# binary_clock.net
KiCad netlist of a schematic drawn in EAGLE
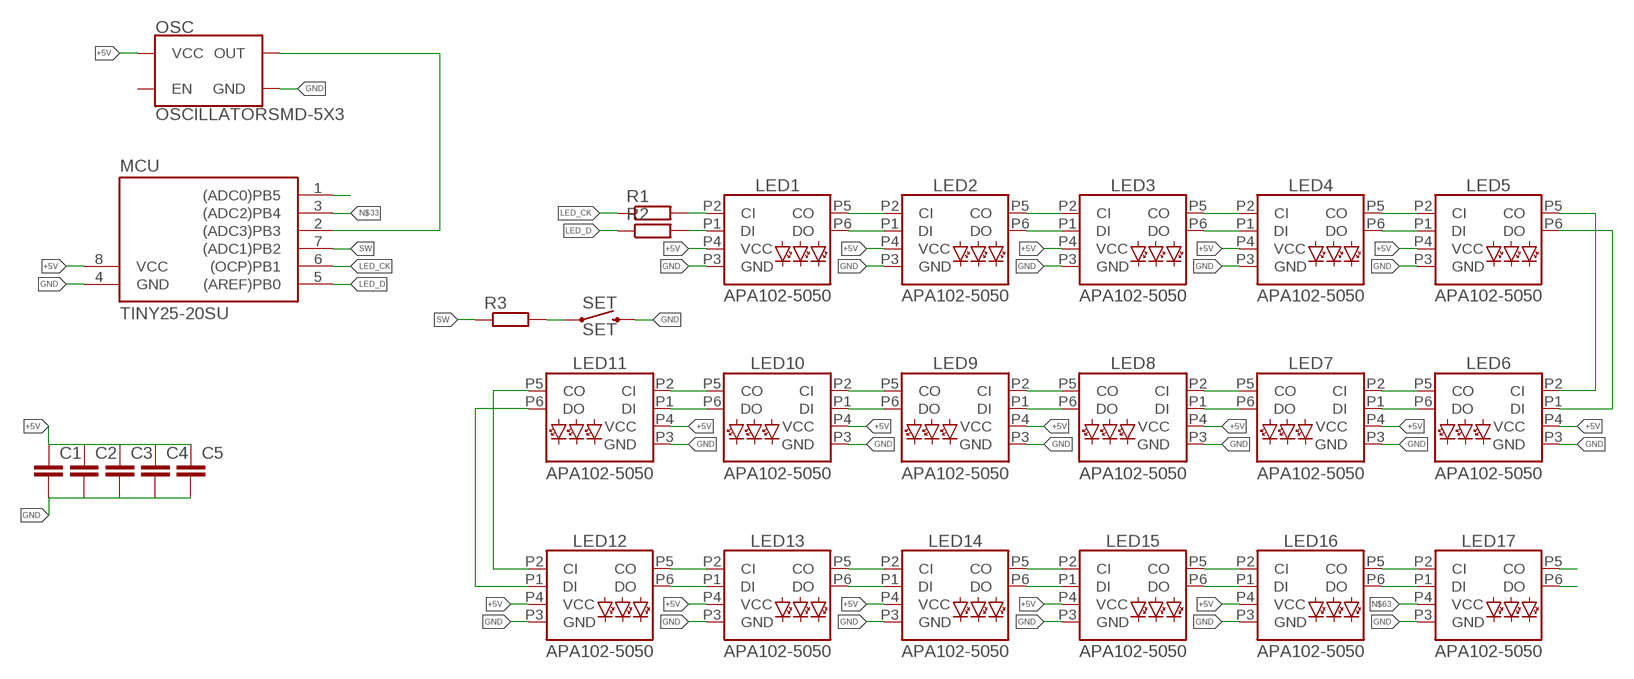
[diagram p0: schematic, sheet 1]

(export (version "E")
  (design (tool "Eeschema 10.0.6"))
  (components
    (comp (ref "C1")
      (value "C-EUC0603K")
      (footprint "eagle-import:C0603K")
      (libsource (lib "eagle-import") (part "C-EUC0603K"))
    )
    (comp (ref "C2")
      (value "C-EUC0603K")
      (footprint "eagle-import:C0603K")
      (libsource (lib "eagle-import") (part "C-EUC0603K"))
    )
    (comp (ref "C3")
      (value "C-EUC0603K")
      (footprint "eagle-import:C0603K")
      (libsource (lib "eagle-import") (part "C-EUC0603K"))
    )
    (comp (ref "C4")
      (value "C-EUC0603K")
      (footprint "eagle-import:C0603K")
      (libsource (lib "eagle-import") (part "C-EUC0603K"))
    )
    (comp (ref "C5")
      (value "C-EUC0603K")
      (footprint "eagle-import:C0603K")
      (libsource (lib "eagle-import") (part "C-EUC0603K"))
    )
    (comp (ref "LED1")
      (value "APA102-5050")
      (footprint "eagle-import:APA102-5050")
      (libsource (lib "eagle-import") (part "APA102-5050"))
    )
    (comp (ref "LED2")
      (value "APA102-5050")
      (footprint "eagle-import:APA102-5050")
      (libsource (lib "eagle-import") (part "APA102-5050"))
    )
    (comp (ref "LED3")
      (value "APA102-5050")
      (footprint "eagle-import:APA102-5050")
      (libsource (lib "eagle-import") (part "APA102-5050"))
    )
    (comp (ref "LED4")
      (value "APA102-5050")
      (footprint "eagle-import:APA102-5050")
      (libsource (lib "eagle-import") (part "APA102-5050"))
    )
    (comp (ref "LED5")
      (value "APA102-5050")
      (footprint "eagle-import:APA102-5050")
      (libsource (lib "eagle-import") (part "APA102-5050"))
    )
    (comp (ref "LED6")
      (value "APA102-5050")
      (footprint "eagle-import:APA102-5050")
      (libsource (lib "eagle-import") (part "APA102-5050"))
    )
    (comp (ref "LED7")
      (value "APA102-5050")
      (footprint "eagle-import:APA102-5050")
      (libsource (lib "eagle-import") (part "APA102-5050"))
    )
    (comp (ref "LED8")
      (value "APA102-5050")
      (footprint "eagle-import:APA102-5050")
      (libsource (lib "eagle-import") (part "APA102-5050"))
    )
    (comp (ref "LED9")
      (value "APA102-5050")
      (footprint "eagle-import:APA102-5050")
      (libsource (lib "eagle-import") (part "APA102-5050"))
    )
    (comp (ref "LED10")
      (value "APA102-5050")
      (footprint "eagle-import:APA102-5050")
      (libsource (lib "eagle-import") (part "APA102-5050"))
    )
    (comp (ref "LED11")
      (value "APA102-5050")
      (footprint "eagle-import:APA102-5050")
      (libsource (lib "eagle-import") (part "APA102-5050"))
    )
    (comp (ref "LED12")
      (value "APA102-5050")
      (footprint "eagle-import:APA102-5050")
      (libsource (lib "eagle-import") (part "APA102-5050"))
    )
    (comp (ref "LED13")
      (value "APA102-5050")
      (footprint "eagle-import:APA102-5050")
      (libsource (lib "eagle-import") (part "APA102-5050"))
    )
    (comp (ref "LED14")
      (value "APA102-5050")
      (footprint "eagle-import:APA102-5050")
      (libsource (lib "eagle-import") (part "APA102-5050"))
    )
    (comp (ref "LED15")
      (value "APA102-5050")
      (footprint "eagle-import:APA102-5050")
      (libsource (lib "eagle-import") (part "APA102-5050"))
    )
    (comp (ref "LED16")
      (value "APA102-5050")
      (footprint "eagle-import:APA102-5050")
      (libsource (lib "eagle-import") (part "APA102-5050"))
    )
    (comp (ref "LED17")
      (value "APA102-5050")
      (footprint "eagle-import:APA102-5050")
      (libsource (lib "eagle-import") (part "APA102-5050"))
    )
    (comp (ref "MCU")
      (value "TINY25-20SU")
      (footprint "eagle-import:SOIC8")
      (libsource (lib "eagle-import") (part "TINY25-20SU"))
    )
    (comp (ref "OSC")
      (value "OSCILLATORSMD-5X3")
      (footprint "eagle-import:OSCILLATOR-SMD-5X3.2")
      (libsource (lib "eagle-import") (part "OSCILLATORSMD-5X3"))
    )
    (comp (ref "R1")
      (value "R-EU_R1206")
      (footprint "eagle-import:R1206")
      (libsource (lib "eagle-import") (part "R-EU_R1206"))
    )
    (comp (ref "R2")
      (value "R-EU_R1206")
      (footprint "eagle-import:R1206")
      (libsource (lib "eagle-import") (part "R-EU_R1206"))
    )
    (comp (ref "R3")
      (value "R-EU_R1206")
      (footprint "eagle-import:R1206")
      (libsource (lib "eagle-import") (part "R-EU_R1206"))
    )
    (comp (ref "SET")
      (value "SET")
      (footprint "eagle-import:TACTILE_SWITCH_SMD_5.2MM")
      (libsource (lib "eagle-import") (part "MOMENTARY-SWITCH-SPST-SMD-5.2-REDUNDANT"))
    )
  )
  (nets
    (net (code "1") (name "+5V") (class "Default")
      (node (ref "C1") (pin "1") (pinfunction "1_1") (pintype "passive"))
      (node (ref "C2") (pin "1") (pinfunction "1_1") (pintype "passive"))
      (node (ref "C3") (pin "1") (pinfunction "1_1") (pintype "passive"))
      (node (ref "C4") (pin "1") (pinfunction "1_1") (pintype "passive"))
      (node (ref "C5") (pin "1") (pinfunction "1_1") (pintype "passive"))
      (node (ref "LED1") (pin "P4") (pinfunction "VCC_P4") (pintype "bidirectional"))
      (node (ref "LED10") (pin "P4") (pinfunction "VCC_P4") (pintype "bidirectional"))
      (node (ref "LED11") (pin "P4") (pinfunction "VCC_P4") (pintype "bidirectional"))
      (node (ref "LED12") (pin "P4") (pinfunction "VCC_P4") (pintype "bidirectional"))
      (node (ref "LED13") (pin "P4") (pinfunction "VCC_P4") (pintype "bidirectional"))
      (node (ref "LED14") (pin "P4") (pinfunction "VCC_P4") (pintype "bidirectional"))
      (node (ref "LED15") (pin "P4") (pinfunction "VCC_P4") (pintype "bidirectional"))
      (node (ref "LED16") (pin "P4") (pinfunction "VCC_P4") (pintype "bidirectional"))
      (node (ref "LED2") (pin "P4") (pinfunction "VCC_P4") (pintype "bidirectional"))
      (node (ref "LED3") (pin "P4") (pinfunction "VCC_P4") (pintype "bidirectional"))
      (node (ref "LED4") (pin "P4") (pinfunction "VCC_P4") (pintype "bidirectional"))
      (node (ref "LED5") (pin "P4") (pinfunction "VCC_P4") (pintype "bidirectional"))
      (node (ref "LED6") (pin "P4") (pinfunction "VCC_P4") (pintype "bidirectional"))
      (node (ref "LED7") (pin "P4") (pinfunction "VCC_P4") (pintype "bidirectional"))
      (node (ref "LED8") (pin "P4") (pinfunction "VCC_P4") (pintype "bidirectional"))
      (node (ref "LED9") (pin "P4") (pinfunction "VCC_P4") (pintype "bidirectional"))
      (node (ref "MCU") (pin "8") (pinfunction "VCC_8") (pintype "power_in"))
      (node (ref "OSC") (pin "4") (pinfunction "VCC_4") (pintype "bidirectional"))
    )
    (net (code "2") (name "GND") (class "Default")
      (node (ref "C1") (pin "2") (pinfunction "2_2") (pintype "passive"))
      (node (ref "C2") (pin "2") (pinfunction "2_2") (pintype "passive"))
      (node (ref "C3") (pin "2") (pinfunction "2_2") (pintype "passive"))
      (node (ref "C4") (pin "2") (pinfunction "2_2") (pintype "passive"))
      (node (ref "C5") (pin "2") (pinfunction "2_2") (pintype "passive"))
      (node (ref "LED1") (pin "P3") (pinfunction "GND_P3") (pintype "bidirectional"))
      (node (ref "LED10") (pin "P3") (pinfunction "GND_P3") (pintype "bidirectional"))
      (node (ref "LED11") (pin "P3") (pinfunction "GND_P3") (pintype "bidirectional"))
      (node (ref "LED12") (pin "P3") (pinfunction "GND_P3") (pintype "bidirectional"))
      (node (ref "LED13") (pin "P3") (pinfunction "GND_P3") (pintype "bidirectional"))
      (node (ref "LED14") (pin "P3") (pinfunction "GND_P3") (pintype "bidirectional"))
      (node (ref "LED15") (pin "P3") (pinfunction "GND_P3") (pintype "bidirectional"))
      (node (ref "LED16") (pin "P3") (pinfunction "GND_P3") (pintype "bidirectional"))
      (node (ref "LED17") (pin "P3") (pinfunction "GND_P3") (pintype "bidirectional"))
      (node (ref "LED2") (pin "P3") (pinfunction "GND_P3") (pintype "bidirectional"))
      (node (ref "LED3") (pin "P3") (pinfunction "GND_P3") (pintype "bidirectional"))
      (node (ref "LED4") (pin "P3") (pinfunction "GND_P3") (pintype "bidirectional"))
      (node (ref "LED5") (pin "P3") (pinfunction "GND_P3") (pintype "bidirectional"))
      (node (ref "LED6") (pin "P3") (pinfunction "GND_P3") (pintype "bidirectional"))
      (node (ref "LED7") (pin "P3") (pinfunction "GND_P3") (pintype "bidirectional"))
      (node (ref "LED8") (pin "P3") (pinfunction "GND_P3") (pintype "bidirectional"))
      (node (ref "LED9") (pin "P3") (pinfunction "GND_P3") (pintype "bidirectional"))
      (node (ref "MCU") (pin "4") (pinfunction "GND_4") (pintype "power_in"))
      (node (ref "OSC") (pin "2") (pinfunction "GND_2") (pintype "bidirectional"))
      (node (ref "SET") (pin "3") (pinfunction "2_3") (pintype "passive"))
      (node (ref "SET") (pin "4") (pinfunction "2_4") (pintype "passive"))
    )
    (net (code "3") (name "LED_CK") (class "Default")
      (node (ref "MCU") (pin "6") (pinfunction "(OCP)PB1_6") (pintype "bidirectional"))
      (node (ref "R1") (pin "1") (pinfunction "1_1") (pintype "passive"))
    )
    (net (code "4") (name "LED_D") (class "Default")
      (node (ref "MCU") (pin "5") (pinfunction "(AREF)PB0_5") (pintype "bidirectional"))
      (node (ref "R2") (pin "1") (pinfunction "1_1") (pintype "passive"))
    )
    (net (code "5") (name "N$33") (class "Default")
      (node (ref "MCU") (pin "3") (pinfunction "(ADC2)PB4_3") (pintype "bidirectional"))
    )
    (net (code "6") (name "N$63") (class "Default")
      (node (ref "LED17") (pin "P4") (pinfunction "VCC_P4") (pintype "bidirectional"))
    )
    (net (code "7") (name "Net-(LED1-CI)") (class "Default")
      (node (ref "LED1") (pin "P2") (pinfunction "CI_P2") (pintype "bidirectional"))
      (node (ref "R1") (pin "2") (pinfunction "2_2") (pintype "passive"))
    )
    (net (code "8") (name "Net-(LED1-CO)") (class "Default")
      (node (ref "LED1") (pin "P5") (pinfunction "CO_P5") (pintype "bidirectional"))
      (node (ref "LED2") (pin "P2") (pinfunction "CI_P2") (pintype "bidirectional"))
    )
    (net (code "9") (name "Net-(LED1-DI)") (class "Default")
      (node (ref "LED1") (pin "P1") (pinfunction "DI_P1") (pintype "bidirectional"))
      (node (ref "R2") (pin "2") (pinfunction "2_2") (pintype "passive"))
    )
    (net (code "10") (name "Net-(LED1-DO)") (class "Default")
      (node (ref "LED1") (pin "P6") (pinfunction "DO_P6") (pintype "bidirectional"))
      (node (ref "LED2") (pin "P1") (pinfunction "DI_P1") (pintype "bidirectional"))
    )
    (net (code "11") (name "Net-(LED2-CO)") (class "Default")
      (node (ref "LED2") (pin "P5") (pinfunction "CO_P5") (pintype "bidirectional"))
      (node (ref "LED3") (pin "P2") (pinfunction "CI_P2") (pintype "bidirectional"))
    )
    (net (code "12") (name "Net-(LED2-DO)") (class "Default")
      (node (ref "LED2") (pin "P6") (pinfunction "DO_P6") (pintype "bidirectional"))
      (node (ref "LED3") (pin "P1") (pinfunction "DI_P1") (pintype "bidirectional"))
    )
    (net (code "13") (name "Net-(LED3-CO)") (class "Default")
      (node (ref "LED3") (pin "P5") (pinfunction "CO_P5") (pintype "bidirectional"))
      (node (ref "LED4") (pin "P2") (pinfunction "CI_P2") (pintype "bidirectional"))
    )
    (net (code "14") (name "Net-(LED3-DO)") (class "Default")
      (node (ref "LED3") (pin "P6") (pinfunction "DO_P6") (pintype "bidirectional"))
      (node (ref "LED4") (pin "P1") (pinfunction "DI_P1") (pintype "bidirectional"))
    )
    (net (code "15") (name "Net-(LED4-CO)") (class "Default")
      (node (ref "LED4") (pin "P5") (pinfunction "CO_P5") (pintype "bidirectional"))
      (node (ref "LED5") (pin "P2") (pinfunction "CI_P2") (pintype "bidirectional"))
    )
    (net (code "16") (name "Net-(LED4-DO)") (class "Default")
      (node (ref "LED4") (pin "P6") (pinfunction "DO_P6") (pintype "bidirectional"))
      (node (ref "LED5") (pin "P1") (pinfunction "DI_P1") (pintype "bidirectional"))
    )
    (net (code "17") (name "Net-(LED5-CO)") (class "Default")
      (node (ref "LED5") (pin "P5") (pinfunction "CO_P5") (pintype "bidirectional"))
      (node (ref "LED6") (pin "P2") (pinfunction "CI_P2") (pintype "bidirectional"))
    )
    (net (code "18") (name "Net-(LED5-DO)") (class "Default")
      (node (ref "LED5") (pin "P6") (pinfunction "DO_P6") (pintype "bidirectional"))
      (node (ref "LED6") (pin "P1") (pinfunction "DI_P1") (pintype "bidirectional"))
    )
    (net (code "19") (name "Net-(LED6-CO)") (class "Default")
      (node (ref "LED6") (pin "P5") (pinfunction "CO_P5") (pintype "bidirectional"))
      (node (ref "LED7") (pin "P2") (pinfunction "CI_P2") (pintype "bidirectional"))
    )
    (net (code "20") (name "Net-(LED6-DO)") (class "Default")
      (node (ref "LED6") (pin "P6") (pinfunction "DO_P6") (pintype "bidirectional"))
      (node (ref "LED7") (pin "P1") (pinfunction "DI_P1") (pintype "bidirectional"))
    )
    (net (code "21") (name "Net-(LED7-CO)") (class "Default")
      (node (ref "LED7") (pin "P5") (pinfunction "CO_P5") (pintype "bidirectional"))
      (node (ref "LED8") (pin "P2") (pinfunction "CI_P2") (pintype "bidirectional"))
    )
    (net (code "22") (name "Net-(LED7-DO)") (class "Default")
      (node (ref "LED7") (pin "P6") (pinfunction "DO_P6") (pintype "bidirectional"))
      (node (ref "LED8") (pin "P1") (pinfunction "DI_P1") (pintype "bidirectional"))
    )
    (net (code "23") (name "Net-(LED8-CO)") (class "Default")
      (node (ref "LED8") (pin "P5") (pinfunction "CO_P5") (pintype "bidirectional"))
      (node (ref "LED9") (pin "P2") (pinfunction "CI_P2") (pintype "bidirectional"))
    )
    (net (code "24") (name "Net-(LED8-DO)") (class "Default")
      (node (ref "LED8") (pin "P6") (pinfunction "DO_P6") (pintype "bidirectional"))
      (node (ref "LED9") (pin "P1") (pinfunction "DI_P1") (pintype "bidirectional"))
    )
    (net (code "25") (name "Net-(LED10-CI)") (class "Default")
      (node (ref "LED10") (pin "P2") (pinfunction "CI_P2") (pintype "bidirectional"))
      (node (ref "LED9") (pin "P5") (pinfunction "CO_P5") (pintype "bidirectional"))
    )
    (net (code "26") (name "Net-(LED10-CO)") (class "Default")
      (node (ref "LED10") (pin "P5") (pinfunction "CO_P5") (pintype "bidirectional"))
      (node (ref "LED11") (pin "P2") (pinfunction "CI_P2") (pintype "bidirectional"))
    )
    (net (code "27") (name "Net-(LED10-DI)") (class "Default")
      (node (ref "LED10") (pin "P1") (pinfunction "DI_P1") (pintype "bidirectional"))
      (node (ref "LED9") (pin "P6") (pinfunction "DO_P6") (pintype "bidirectional"))
    )
    (net (code "28") (name "Net-(LED10-DO)") (class "Default")
      (node (ref "LED10") (pin "P6") (pinfunction "DO_P6") (pintype "bidirectional"))
      (node (ref "LED11") (pin "P1") (pinfunction "DI_P1") (pintype "bidirectional"))
    )
    (net (code "29") (name "Net-(LED11-CO)") (class "Default")
      (node (ref "LED11") (pin "P5") (pinfunction "CO_P5") (pintype "bidirectional"))
      (node (ref "LED12") (pin "P2") (pinfunction "CI_P2") (pintype "bidirectional"))
    )
    (net (code "30") (name "Net-(LED11-DO)") (class "Default")
      (node (ref "LED11") (pin "P6") (pinfunction "DO_P6") (pintype "bidirectional"))
      (node (ref "LED12") (pin "P1") (pinfunction "DI_P1") (pintype "bidirectional"))
    )
    (net (code "31") (name "Net-(LED12-CO)") (class "Default")
      (node (ref "LED12") (pin "P5") (pinfunction "CO_P5") (pintype "bidirectional"))
      (node (ref "LED13") (pin "P2") (pinfunction "CI_P2") (pintype "bidirectional"))
    )
    (net (code "32") (name "Net-(LED12-DO)") (class "Default")
      (node (ref "LED12") (pin "P6") (pinfunction "DO_P6") (pintype "bidirectional"))
      (node (ref "LED13") (pin "P1") (pinfunction "DI_P1") (pintype "bidirectional"))
    )
    (net (code "33") (name "Net-(LED13-CO)") (class "Default")
      (node (ref "LED13") (pin "P5") (pinfunction "CO_P5") (pintype "bidirectional"))
      (node (ref "LED14") (pin "P2") (pinfunction "CI_P2") (pintype "bidirectional"))
    )
    (net (code "34") (name "Net-(LED13-DO)") (class "Default")
      (node (ref "LED13") (pin "P6") (pinfunction "DO_P6") (pintype "bidirectional"))
      (node (ref "LED14") (pin "P1") (pinfunction "DI_P1") (pintype "bidirectional"))
    )
    (net (code "35") (name "Net-(LED14-CO)") (class "Default")
      (node (ref "LED14") (pin "P5") (pinfunction "CO_P5") (pintype "bidirectional"))
      (node (ref "LED15") (pin "P2") (pinfunction "CI_P2") (pintype "bidirectional"))
    )
    (net (code "36") (name "Net-(LED14-DO)") (class "Default")
      (node (ref "LED14") (pin "P6") (pinfunction "DO_P6") (pintype "bidirectional"))
      (node (ref "LED15") (pin "P1") (pinfunction "DI_P1") (pintype "bidirectional"))
    )
    (net (code "37") (name "Net-(LED15-CO)") (class "Default")
      (node (ref "LED15") (pin "P5") (pinfunction "CO_P5") (pintype "bidirectional"))
      (node (ref "LED16") (pin "P2") (pinfunction "CI_P2") (pintype "bidirectional"))
    )
    (net (code "38") (name "Net-(LED15-DO)") (class "Default")
      (node (ref "LED15") (pin "P6") (pinfunction "DO_P6") (pintype "bidirectional"))
      (node (ref "LED16") (pin "P1") (pinfunction "DI_P1") (pintype "bidirectional"))
    )
    (net (code "39") (name "Net-(LED16-CO)") (class "Default")
      (node (ref "LED16") (pin "P5") (pinfunction "CO_P5") (pintype "bidirectional"))
      (node (ref "LED17") (pin "P2") (pinfunction "CI_P2") (pintype "bidirectional"))
    )
    (net (code "40") (name "Net-(LED16-DO)") (class "Default")
      (node (ref "LED16") (pin "P6") (pinfunction "DO_P6") (pintype "bidirectional"))
      (node (ref "LED17") (pin "P1") (pinfunction "DI_P1") (pintype "bidirectional"))
    )
    (net (code "41") (name "Net-(MCU-(ADC3)PB3)") (class "Default")
      (node (ref "MCU") (pin "2") (pinfunction "(ADC3)PB3_2") (pintype "bidirectional"))
      (node (ref "OSC") (pin "3") (pinfunction "OUT_3") (pintype "bidirectional"))
    )
    (net (code "42") (name "Net-(R3-Pad2)") (class "Default")
      (node (ref "R3") (pin "2") (pinfunction "2_2") (pintype "passive"))
      (node (ref "SET") (pin "1") (pinfunction "1_1") (pintype "passive"))
      (node (ref "SET") (pin "2") (pinfunction "1_2") (pintype "passive"))
    )
    (net (code "43") (name "SW") (class "Default")
      (node (ref "MCU") (pin "7") (pinfunction "(ADC1)PB2_7") (pintype "bidirectional"))
      (node (ref "R3") (pin "1") (pinfunction "1_1") (pintype "passive"))
    )
    (net (code "44") (name "unconnected-(LED17-CO-PadP5)") (class "Default")
      (node (ref "LED17") (pin "P5") (pinfunction "CO_P5") (pintype "bidirectional"))
    )
    (net (code "45") (name "unconnected-(LED17-DO-PadP6)") (class "Default")
      (node (ref "LED17") (pin "P6") (pinfunction "DO_P6") (pintype "bidirectional"))
    )
    (net (code "46") (name "unconnected-(MCU-(ADC0)PB5-Pad1)") (class "Default")
      (node (ref "MCU") (pin "1") (pinfunction "(ADC0)PB5_1") (pintype "bidirectional"))
    )
    (net (code "47") (name "unconnected-(OSC-EN-Pad1)") (class "Default")
      (node (ref "OSC") (pin "1") (pinfunction "EN_1") (pintype "bidirectional"))
    )
  )
)
